# 1_Calculation_and_search_of_the_working_.net
KiCad netlist of a schematic drawn in Altium Designer
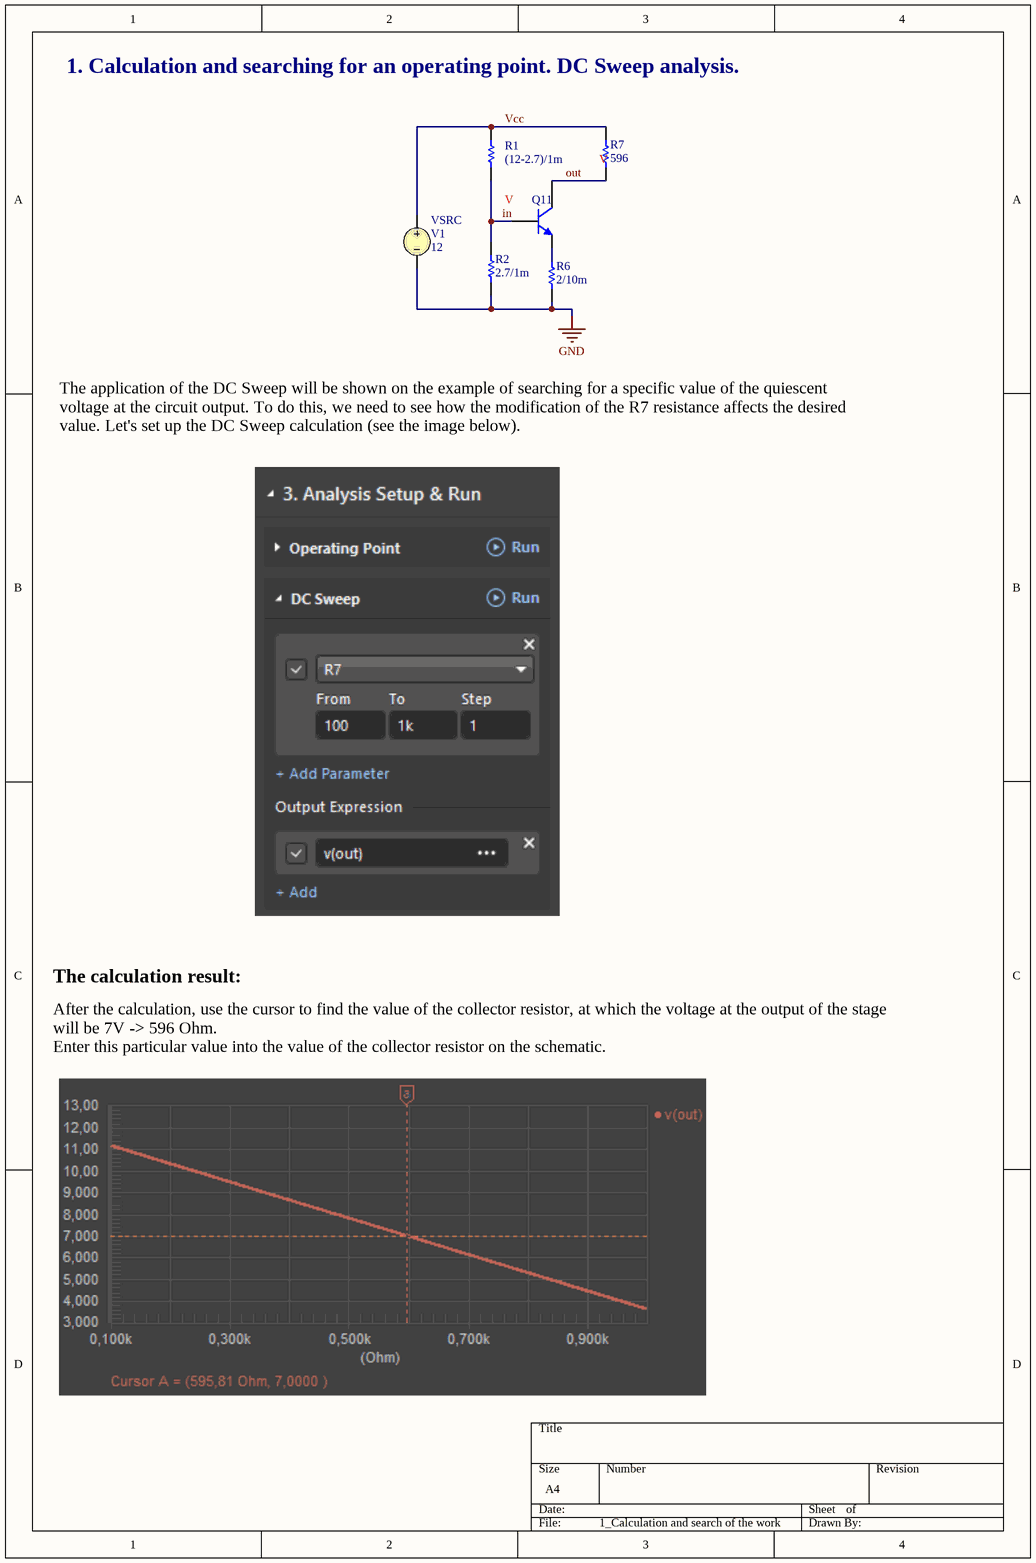
[diagram p0: 1_Calculation and search of the working point.SchDoc]

(export (version "E")
  (design (tool "Eeschema 10.0.6"))
  (components
    (comp (ref "Q11")
      (value "Bipolar  NPN 3 Pins  Transistor  Modified Version of the Gummel-Poon Model")
      (libsource (lib "Simulation Generic Components") (part "BJT NPN_MGP"))
    )
    (comp (ref "R1")
      (value "(12-2.7)/1m")
      (description "Resistor")
      (libsource (lib "Simulation Generic Components") (part "Resistor"))
    )
    (comp (ref "R2")
      (value "2.7/1m")
      (description "Resistor")
      (libsource (lib "Simulation Generic Components") (part "Resistor"))
    )
    (comp (ref "R6")
      (value "2/10m")
      (description "Resistor")
      (libsource (lib "Simulation Generic Components") (part "Resistor"))
    )
    (comp (ref "R7")
      (value "596")
      (description "Resistor")
      (libsource (lib "Simulation Generic Components") (part "Resistor"))
    )
    (comp (ref "V1")
      (value "VSRC")
      (description "Voltage Source")
      (fields (field (name "ALTIUM_VALUE") "12") (field (name "PUBLISHER") "Altium Limited"))
      (libsource (lib "Simulation Generic Components") (part "VSRC"))
    )
  )
  (nets
    (net (code "1") (name "/Vcc") (class "Default")
      (node (ref "R1") (pin "2") (pinfunction "2_2") (pintype "passive"))
      (node (ref "R7") (pin "2") (pinfunction "2_2") (pintype "passive"))
      (node (ref "V1") (pin "1") (pinfunction "1_1") (pintype "passive"))
    )
    (net (code "2") (name "/in") (class "Default")
      (node (ref "Q11") (pin "2") (pinfunction "B_2") (pintype "passive"))
      (node (ref "R1") (pin "1") (pinfunction "1_1") (pintype "passive"))
      (node (ref "R2") (pin "1") (pinfunction "1_1") (pintype "passive"))
    )
    (net (code "3") (name "/out") (class "Default")
      (node (ref "Q11") (pin "1") (pinfunction "C_1") (pintype "passive"))
      (node (ref "R7") (pin "1") (pinfunction "1_1") (pintype "passive"))
    )
    (net (code "4") (name "GND") (class "Default")
      (node (ref "R2") (pin "2") (pinfunction "2_2") (pintype "passive"))
      (node (ref "R6") (pin "1") (pinfunction "1_1") (pintype "passive"))
      (node (ref "V1") (pin "2") (pinfunction "2_2") (pintype "passive"))
    )
    (net (code "5") (name "Net-(Q11-E)") (class "Default")
      (node (ref "Q11") (pin "3") (pinfunction "E_3") (pintype "passive"))
      (node (ref "R6") (pin "2") (pinfunction "2_2") (pintype "passive"))
    )
  )
)
